# VUE_PIC32_v1_0_Analog_4X.net
KiCad netlist of a schematic drawn in Altium Designer
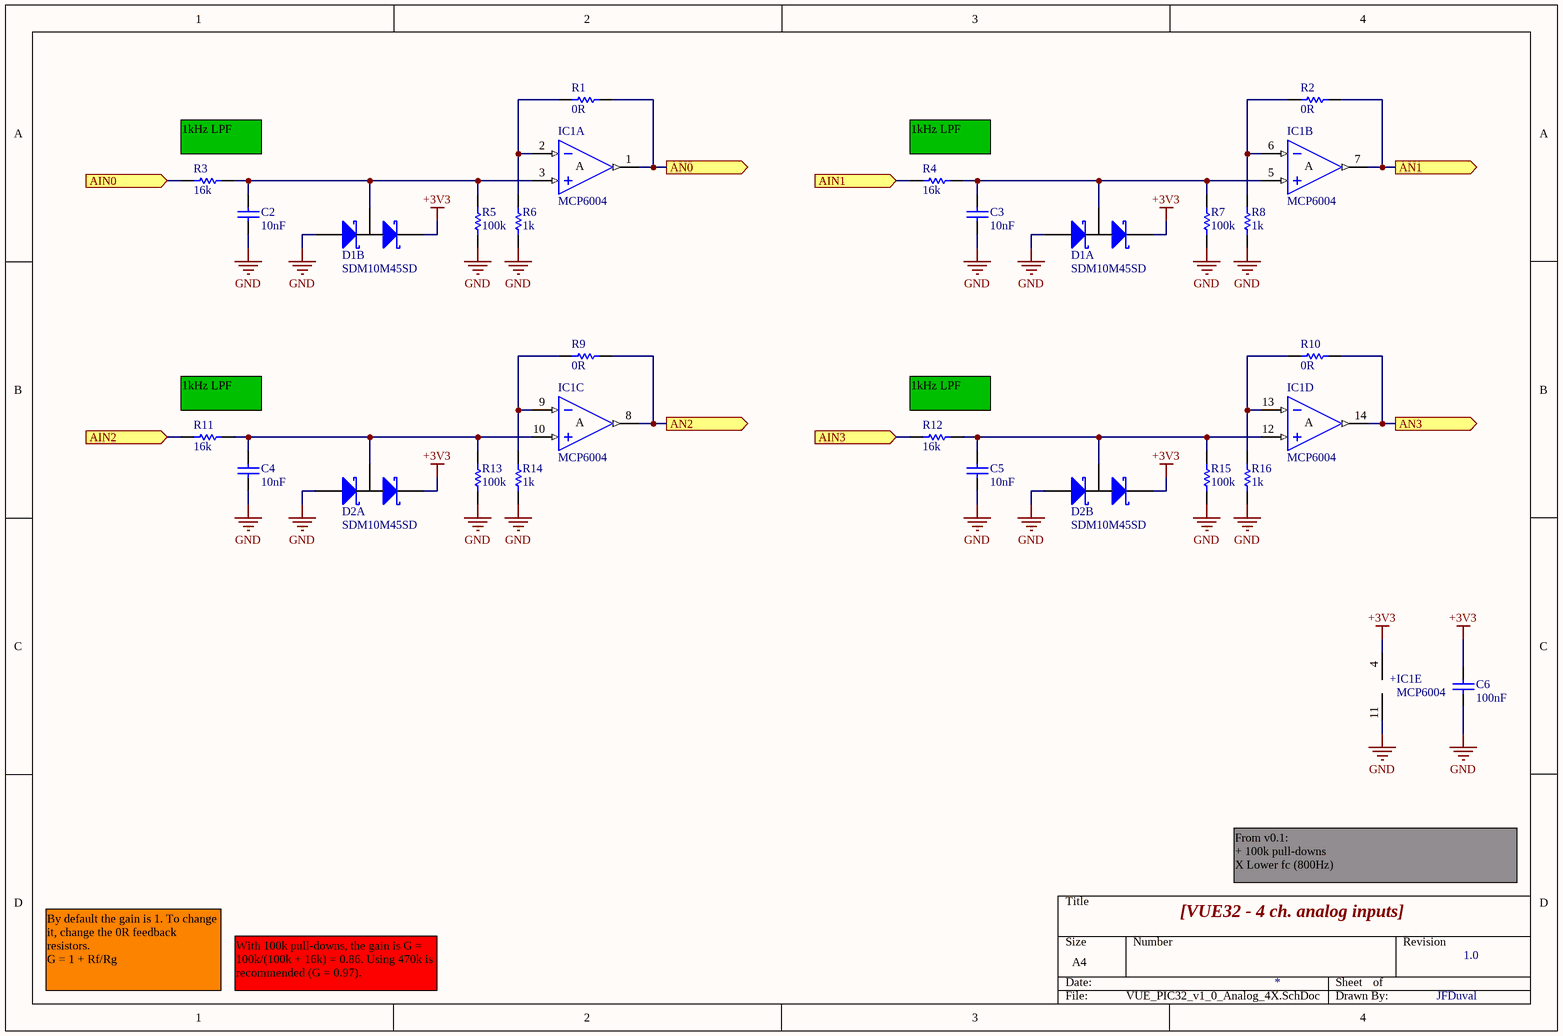
[diagram p0: VUE_PIC32_v1_0_Analog_4X.SchDoc]

(export (version "E")
  (design (tool "Eeschema 10.0.6"))
  (components
    (comp (ref "C2")
      (value "10nF")
      (footprint "0402C")
      (description "CAP CER 10000PF 25V 10% X7R 0402")
      (fields (field (name "MFG") "TDK") (field (name "MFGPARTNUMBER") "C1005X7R1E103K"))
      (libsource (lib "JFD_Cap") (part "CAP_TDK_C_0402_10nF_25V"))
    )
    (comp (ref "C3")
      (value "10nF")
      (footprint "0402C")
      (description "CAP CER 10000PF 25V 10% X7R 0402")
      (fields (field (name "MFG") "TDK") (field (name "MFGPARTNUMBER") "C1005X7R1E103K"))
      (libsource (lib "JFD_Cap") (part "CAP_TDK_C_0402_10nF_25V"))
    )
    (comp (ref "C4")
      (value "10nF")
      (footprint "0402C")
      (description "CAP CER 10000PF 25V 10% X7R 0402")
      (fields (field (name "MFG") "TDK") (field (name "MFGPARTNUMBER") "C1005X7R1E103K"))
      (libsource (lib "JFD_Cap") (part "CAP_TDK_C_0402_10nF_25V"))
    )
    (comp (ref "C5")
      (value "10nF")
      (footprint "0402C")
      (description "CAP CER 10000PF 25V 10% X7R 0402")
      (fields (field (name "MFG") "TDK") (field (name "MFGPARTNUMBER") "C1005X7R1E103K"))
      (libsource (lib "JFD_Cap") (part "CAP_TDK_C_0402_10nF_25V"))
    )
    (comp (ref "C6")
      (value "100nF")
      (footprint "0402C")
      (description "CAP CER 0.1UF 25V Y5V 0402")
      (fields (field (name "MFG") "TDK") (field (name "MFGPARTNUMBER") "C1005Y5V1E104Z"))
      (libsource (lib "JFD_Cap") (part "CAP_TDK_C_0402_100nF_25V"))
    )
    (comp (ref "D1")
      (value "SDM10M45SD")
      (footprint "SOT23-6")
      (description "DIODE SCHOTTKY ARRAY 45V SOT26")
      (fields (field (name "MFG") "Diodes Inc") (field (name "MFGPARTNUMBER") "SDM10M45SD-7-F"))
      (libsource (lib "JFD_Semi") (part "DIODE_DIODESINC_SDM10M45SD_QUAD_SCHOTTKY_45V_200MA"))
    )
    (comp (ref "D2")
      (value "SDM10M45SD")
      (footprint "SOT23-6")
      (description "DIODE SCHOTTKY ARRAY 45V SOT26")
      (fields (field (name "MFG") "Diodes Inc") (field (name "MFGPARTNUMBER") "SDM10M45SD-7-F"))
      (libsource (lib "JFD_Semi") (part "DIODE_DIODESINC_SDM10M45SD_QUAD_SCHOTTKY_45V_200MA"))
    )
    (comp (ref "IC1")
      (value "MCP6004")
      (footprint "TSSOP14")
      (description "IC OPAMP QUAD 1.8V 14TSSOP")
      (fields (field (name "MFG") "Microchip Technology") (field (name "MFGPARTNUMBER") "MCP6004-I/ST"))
      (libsource (lib "JFD_IC") (part "IC_OPA_MICROCHIP_MCP6004_QUAD_TSSOP14"))
    )
    (comp (ref "R1")
      (value "0R")
      (footprint "0402")
      (description "RES 0.0 OHM 1/16W 0402 SMD")
      (fields (field (name "MFG") "Yageo") (field (name "MFGPARTNUMBER") "RC0402JR-070RL"))
      (libsource (lib "JFD_Res") (part "RES_YAGEO_0402_0R_1PCT"))
    )
    (comp (ref "R2")
      (value "0R")
      (footprint "0402")
      (description "RES 0.0 OHM 1/16W 0402 SMD")
      (fields (field (name "MFG") "Yageo") (field (name "MFGPARTNUMBER") "RC0402JR-070RL"))
      (libsource (lib "JFD_Res") (part "RES_YAGEO_0402_0R_1PCT"))
    )
    (comp (ref "R3")
      (value "16k")
      (footprint "0402")
      (description "RES 16.0K OHM 1/16W 1% 0402 SMD")
      (fields (field (name "MFG") "Yageo") (field (name "MFGPARTNUMBER") "RC0402FR-0716KL"))
      (libsource (lib "JFD_Res") (part "RES_YAGEO_0402_16K_1PCT"))
    )
    (comp (ref "R4")
      (value "16k")
      (footprint "0402")
      (description "RES 16.0K OHM 1/16W 1% 0402 SMD")
      (fields (field (name "MFG") "Yageo") (field (name "MFGPARTNUMBER") "RC0402FR-0716KL"))
      (libsource (lib "JFD_Res") (part "RES_YAGEO_0402_16K_1PCT"))
    )
    (comp (ref "R5")
      (value "100k")
      (footprint "0402")
      (description "RES 100K OHM 1/16W 1% 0402 SMD")
      (fields (field (name "MFG") "Yageo") (field (name "MFGPARTNUMBER") "RC0402FR-07100KL"))
      (libsource (lib "JFD_Res") (part "RES_YAGEO_0402_100K_1PCT"))
    )
    (comp (ref "R6")
      (value "1k")
      (footprint "0402")
      (description "RES 1.00K OHM 1/16W 1% 0402 SMD")
      (fields (field (name "MFG") "Yageo") (field (name "MFGPARTNUMBER") "RC0402FR-071KL"))
      (libsource (lib "JFD_Res") (part "RES_YAGEO_0402_1K_1PCT"))
    )
    (comp (ref "R7")
      (value "100k")
      (footprint "0402")
      (description "RES 100K OHM 1/16W 1% 0402 SMD")
      (fields (field (name "MFG") "Yageo") (field (name "MFGPARTNUMBER") "RC0402FR-07100KL"))
      (libsource (lib "JFD_Res") (part "RES_YAGEO_0402_100K_1PCT"))
    )
    (comp (ref "R8")
      (value "1k")
      (footprint "0402")
      (description "RES 1.00K OHM 1/16W 1% 0402 SMD")
      (fields (field (name "MFG") "Yageo") (field (name "MFGPARTNUMBER") "RC0402FR-071KL"))
      (libsource (lib "JFD_Res") (part "RES_YAGEO_0402_1K_1PCT"))
    )
    (comp (ref "R9")
      (value "0R")
      (footprint "0402")
      (description "RES 0.0 OHM 1/16W 0402 SMD")
      (fields (field (name "MFG") "Yageo") (field (name "MFGPARTNUMBER") "RC0402JR-070RL"))
      (libsource (lib "JFD_Res") (part "RES_YAGEO_0402_0R_1PCT"))
    )
    (comp (ref "R10")
      (value "0R")
      (footprint "0402")
      (description "RES 0.0 OHM 1/16W 0402 SMD")
      (fields (field (name "MFG") "Yageo") (field (name "MFGPARTNUMBER") "RC0402JR-070RL"))
      (libsource (lib "JFD_Res") (part "RES_YAGEO_0402_0R_1PCT"))
    )
    (comp (ref "R11")
      (value "16k")
      (footprint "0402")
      (description "RES 16.0K OHM 1/16W 1% 0402 SMD")
      (fields (field (name "MFG") "Yageo") (field (name "MFGPARTNUMBER") "RC0402FR-0716KL"))
      (libsource (lib "JFD_Res") (part "RES_YAGEO_0402_16K_1PCT"))
    )
    (comp (ref "R12")
      (value "16k")
      (footprint "0402")
      (description "RES 16.0K OHM 1/16W 1% 0402 SMD")
      (fields (field (name "MFG") "Yageo") (field (name "MFGPARTNUMBER") "RC0402FR-0716KL"))
      (libsource (lib "JFD_Res") (part "RES_YAGEO_0402_16K_1PCT"))
    )
    (comp (ref "R13")
      (value "100k")
      (footprint "0402")
      (description "RES 100K OHM 1/16W 1% 0402 SMD")
      (fields (field (name "MFG") "Yageo") (field (name "MFGPARTNUMBER") "RC0402FR-07100KL"))
      (libsource (lib "JFD_Res") (part "RES_YAGEO_0402_100K_1PCT"))
    )
    (comp (ref "R14")
      (value "1k")
      (footprint "0402")
      (description "RES 1.00K OHM 1/16W 1% 0402 SMD")
      (fields (field (name "MFG") "Yageo") (field (name "MFGPARTNUMBER") "RC0402FR-071KL"))
      (libsource (lib "JFD_Res") (part "RES_YAGEO_0402_1K_1PCT"))
    )
    (comp (ref "R15")
      (value "100k")
      (footprint "0402")
      (description "RES 100K OHM 1/16W 1% 0402 SMD")
      (fields (field (name "MFG") "Yageo") (field (name "MFGPARTNUMBER") "RC0402FR-07100KL"))
      (libsource (lib "JFD_Res") (part "RES_YAGEO_0402_100K_1PCT"))
    )
    (comp (ref "R16")
      (value "1k")
      (footprint "0402")
      (description "RES 1.00K OHM 1/16W 1% 0402 SMD")
      (fields (field (name "MFG") "Yageo") (field (name "MFGPARTNUMBER") "RC0402FR-071KL"))
      (libsource (lib "JFD_Res") (part "RES_YAGEO_0402_1K_1PCT"))
    )
  )
  (nets
    (net (code "1") (name "+3V3") (class "Default")
      (node (ref "C6") (pin "2") (pinfunction "2_2") (pintype "passive"))
      (node (ref "D1") (pin "2") (pinfunction "K_2") (pintype "passive"))
      (node (ref "D1") (pin "5") (pinfunction "K_5") (pintype "passive"))
      (node (ref "D2") (pin "2") (pinfunction "K_2") (pintype "passive"))
      (node (ref "D2") (pin "5") (pinfunction "K_5") (pintype "passive"))
      (node (ref "IC1") (pin "4") (pinfunction "VDD_4") (pintype "power_in"))
    )
    (net (code "2") (name "/AIN0") (class "Default")
      (node (ref "R3") (pin "1") (pinfunction "1_1") (pintype "passive"))
    )
    (net (code "3") (name "/AIN1") (class "Default")
      (node (ref "R4") (pin "1") (pinfunction "1_1") (pintype "passive"))
    )
    (net (code "4") (name "/AIN2") (class "Default")
      (node (ref "R11") (pin "1") (pinfunction "1_1") (pintype "passive"))
    )
    (net (code "5") (name "/AIN3") (class "Default")
      (node (ref "R12") (pin "1") (pinfunction "1_1") (pintype "passive"))
    )
    (net (code "6") (name "/AN0") (class "Default")
      (node (ref "IC1") (pin "1") (pinfunction "OUT_1") (pintype "output"))
      (node (ref "R1") (pin "1") (pinfunction "1_1") (pintype "passive"))
    )
    (net (code "7") (name "/AN1") (class "Default")
      (node (ref "IC1") (pin "7") (pinfunction "OUT_7") (pintype "output"))
      (node (ref "R2") (pin "1") (pinfunction "1_1") (pintype "passive"))
    )
    (net (code "8") (name "/AN2") (class "Default")
      (node (ref "IC1") (pin "8") (pinfunction "OUT_8") (pintype "output"))
      (node (ref "R9") (pin "1") (pinfunction "1_1") (pintype "passive"))
    )
    (net (code "9") (name "/AN3") (class "Default")
      (node (ref "IC1") (pin "14") (pinfunction "OUT_14") (pintype "output"))
      (node (ref "R10") (pin "1") (pinfunction "1_1") (pintype "passive"))
    )
    (net (code "10") (name "GND") (class "Default")
      (node (ref "C2") (pin "1") (pinfunction "1_1") (pintype "passive"))
      (node (ref "C3") (pin "1") (pinfunction "1_1") (pintype "passive"))
      (node (ref "C4") (pin "1") (pinfunction "1_1") (pintype "passive"))
      (node (ref "C5") (pin "1") (pinfunction "1_1") (pintype "passive"))
      (node (ref "C6") (pin "1") (pinfunction "1_1") (pintype "passive"))
      (node (ref "D1") (pin "1") (pinfunction "A_1") (pintype "passive"))
      (node (ref "D1") (pin "4") (pinfunction "A_4") (pintype "passive"))
      (node (ref "D2") (pin "1") (pinfunction "A_1") (pintype "passive"))
      (node (ref "D2") (pin "4") (pinfunction "A_4") (pintype "passive"))
      (node (ref "IC1") (pin "11") (pinfunction "VSS_11") (pintype "power_in"))
      (node (ref "R13") (pin "1") (pinfunction "1_1") (pintype "passive"))
      (node (ref "R14") (pin "1") (pinfunction "1_1") (pintype "passive"))
      (node (ref "R15") (pin "1") (pinfunction "1_1") (pintype "passive"))
      (node (ref "R16") (pin "1") (pinfunction "1_1") (pintype "passive"))
      (node (ref "R5") (pin "1") (pinfunction "1_1") (pintype "passive"))
      (node (ref "R6") (pin "1") (pinfunction "1_1") (pintype "passive"))
      (node (ref "R7") (pin "1") (pinfunction "1_1") (pintype "passive"))
      (node (ref "R8") (pin "1") (pinfunction "1_1") (pintype "passive"))
    )
    (net (code "11") (name "Net-(D1A-M)") (class "Default")
      (node (ref "C3") (pin "2") (pinfunction "2_2") (pintype "passive"))
      (node (ref "D1") (pin "6") (pinfunction "M_6") (pintype "passive"))
      (node (ref "IC1") (pin "5") (pinfunction "IN+_5") (pintype "input"))
      (node (ref "R4") (pin "2") (pinfunction "2_2") (pintype "passive"))
      (node (ref "R7") (pin "2") (pinfunction "2_2") (pintype "passive"))
    )
    (net (code "12") (name "Net-(D1B-M)") (class "Default")
      (node (ref "C2") (pin "2") (pinfunction "2_2") (pintype "passive"))
      (node (ref "D1") (pin "3") (pinfunction "M_3") (pintype "passive"))
      (node (ref "IC1") (pin "3") (pinfunction "IN+_3") (pintype "input"))
      (node (ref "R3") (pin "2") (pinfunction "2_2") (pintype "passive"))
      (node (ref "R5") (pin "2") (pinfunction "2_2") (pintype "passive"))
    )
    (net (code "13") (name "Net-(D2A-M)") (class "Default")
      (node (ref "C4") (pin "2") (pinfunction "2_2") (pintype "passive"))
      (node (ref "D2") (pin "6") (pinfunction "M_6") (pintype "passive"))
      (node (ref "IC1") (pin "10") (pinfunction "IN+_10") (pintype "input"))
      (node (ref "R11") (pin "2") (pinfunction "2_2") (pintype "passive"))
      (node (ref "R13") (pin "2") (pinfunction "2_2") (pintype "passive"))
    )
    (net (code "14") (name "Net-(D2B-M)") (class "Default")
      (node (ref "C5") (pin "2") (pinfunction "2_2") (pintype "passive"))
      (node (ref "D2") (pin "3") (pinfunction "M_3") (pintype "passive"))
      (node (ref "IC1") (pin "12") (pinfunction "IN+_12") (pintype "input"))
      (node (ref "R12") (pin "2") (pinfunction "2_2") (pintype "passive"))
      (node (ref "R15") (pin "2") (pinfunction "2_2") (pintype "passive"))
    )
    (net (code "15") (name "Net-(IC1A-IN-)") (class "Default")
      (node (ref "IC1") (pin "2") (pinfunction "IN-_2") (pintype "input"))
      (node (ref "R1") (pin "2") (pinfunction "2_2") (pintype "passive"))
      (node (ref "R6") (pin "2") (pinfunction "2_2") (pintype "passive"))
    )
    (net (code "16") (name "Net-(IC1B-IN-)") (class "Default")
      (node (ref "IC1") (pin "6") (pinfunction "IN-_6") (pintype "input"))
      (node (ref "R2") (pin "2") (pinfunction "2_2") (pintype "passive"))
      (node (ref "R8") (pin "2") (pinfunction "2_2") (pintype "passive"))
    )
    (net (code "17") (name "Net-(IC1C-IN-)") (class "Default")
      (node (ref "IC1") (pin "9") (pinfunction "IN-_9") (pintype "input"))
      (node (ref "R14") (pin "2") (pinfunction "2_2") (pintype "passive"))
      (node (ref "R9") (pin "2") (pinfunction "2_2") (pintype "passive"))
    )
    (net (code "18") (name "Net-(IC1D-IN-)") (class "Default")
      (node (ref "IC1") (pin "13") (pinfunction "IN-_13") (pintype "input"))
      (node (ref "R10") (pin "2") (pinfunction "2_2") (pintype "passive"))
      (node (ref "R16") (pin "2") (pinfunction "2_2") (pintype "passive"))
    )
  )
)
